# redLED.net
KiCad netlist of a schematic drawn in EAGLE
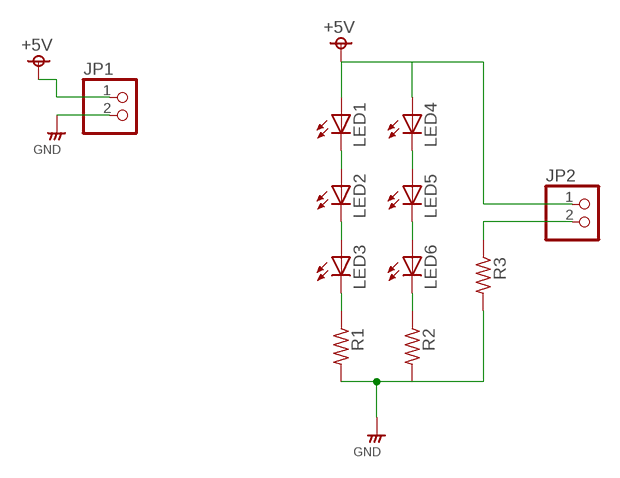
[diagram p0: schematic, sheet 1]

(export (version "E")
  (design (tool "Eeschema 10.0.6"))
  (components
    (comp (ref "JP1")
      (value "PINHD-1X2\"")
      (footprint "eagle-import:1_02")
      (libsource (lib "eagle-import") (part "PINHD-1X2{dblquote}"))
    )
    (comp (ref "JP2")
      (value "PINHD-1X2\"")
      (footprint "eagle-import:1_02")
      (libsource (lib "eagle-import") (part "PINHD-1X2{dblquote}"))
    )
    (comp (ref "LED1")
      (value "LED5MM")
      (footprint "eagle-import:LED5MM")
      (libsource (lib "eagle-import") (part "LED5MM"))
    )
    (comp (ref "LED2")
      (value "LED5MM")
      (footprint "eagle-import:LED5MM")
      (libsource (lib "eagle-import") (part "LED5MM"))
    )
    (comp (ref "LED3")
      (value "LED5MM")
      (footprint "eagle-import:LED5MM")
      (libsource (lib "eagle-import") (part "LED5MM"))
    )
    (comp (ref "LED4")
      (value "LED5MM")
      (footprint "eagle-import:LED5MM")
      (libsource (lib "eagle-import") (part "LED5MM"))
    )
    (comp (ref "LED5")
      (value "LED5MM")
      (footprint "eagle-import:LED5MM")
      (libsource (lib "eagle-import") (part "LED5MM"))
    )
    (comp (ref "LED6")
      (value "LED5MM")
      (footprint "eagle-import:LED5MM")
      (libsource (lib "eagle-import") (part "LED5MM"))
    )
    (comp (ref "R1")
      (value "RESISTORS-3")
      (footprint "eagle-import:R_0.2")
      (libsource (lib "eagle-import") (part "RESISTORS-3"))
    )
    (comp (ref "R2")
      (value "RESISTORS-3")
      (footprint "eagle-import:R_0.2")
      (libsource (lib "eagle-import") (part "RESISTORS-3"))
    )
    (comp (ref "R3")
      (value "RESISTORS-4")
      (footprint "eagle-import:R_0.3")
      (libsource (lib "eagle-import") (part "RESISTORS-4"))
    )
  )
  (nets
    (net (code "1") (name "/+5V") (class "Default")
      (node (ref "JP1") (pin "1") (pinfunction "1_1") (pintype "passive"))
      (node (ref "JP2") (pin "1") (pinfunction "1_1") (pintype "passive"))
      (node (ref "LED1") (pin "A") (pinfunction "A_A") (pintype "passive"))
      (node (ref "LED4") (pin "A") (pinfunction "A_A") (pintype "passive"))
    )
    (net (code "2") (name "GND") (class "Default")
      (node (ref "JP1") (pin "2") (pinfunction "2_2") (pintype "passive"))
      (node (ref "R1") (pin "2") (pinfunction "2_2") (pintype "passive"))
      (node (ref "R2") (pin "2") (pinfunction "2_2") (pintype "passive"))
      (node (ref "R3") (pin "2") (pinfunction "2_2") (pintype "passive"))
    )
    (net (code "3") (name "Net-(JP2-Pad2)") (class "Default")
      (node (ref "JP2") (pin "2") (pinfunction "2_2") (pintype "passive"))
      (node (ref "R3") (pin "1") (pinfunction "1_1") (pintype "passive"))
    )
    (net (code "4") (name "Net-(LED1-C)") (class "Default")
      (node (ref "LED1") (pin "K") (pinfunction "C_K") (pintype "passive"))
      (node (ref "LED2") (pin "A") (pinfunction "A_A") (pintype "passive"))
    )
    (net (code "5") (name "Net-(LED2-C)") (class "Default")
      (node (ref "LED2") (pin "K") (pinfunction "C_K") (pintype "passive"))
      (node (ref "LED3") (pin "A") (pinfunction "A_A") (pintype "passive"))
    )
    (net (code "6") (name "Net-(LED3-C)") (class "Default")
      (node (ref "LED3") (pin "K") (pinfunction "C_K") (pintype "passive"))
      (node (ref "R1") (pin "1") (pinfunction "1_1") (pintype "passive"))
    )
    (net (code "7") (name "Net-(LED4-C)") (class "Default")
      (node (ref "LED4") (pin "K") (pinfunction "C_K") (pintype "passive"))
      (node (ref "LED5") (pin "A") (pinfunction "A_A") (pintype "passive"))
    )
    (net (code "8") (name "Net-(LED5-C)") (class "Default")
      (node (ref "LED5") (pin "K") (pinfunction "C_K") (pintype "passive"))
      (node (ref "LED6") (pin "A") (pinfunction "A_A") (pintype "passive"))
    )
    (net (code "9") (name "Net-(LED6-C)") (class "Default")
      (node (ref "LED6") (pin "K") (pinfunction "C_K") (pintype "passive"))
      (node (ref "R2") (pin "1") (pinfunction "1_1") (pintype "passive"))
    )
  )
)
